# STB_UID.net
KiCad netlist of a schematic drawn in Altium Designer
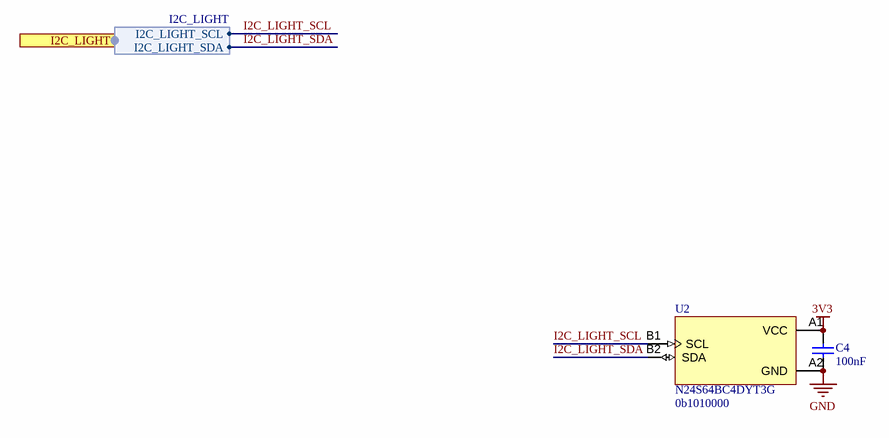
[diagram p0: STB_UID.SchDoc]

(export (version "E")
  (design (tool "Eeschema 10.0.6"))
  (components
    (comp (ref "C4")
      (value "100nF")
      (footprint "CAPC1050X55X23LL05T13")
      (description "Chip Capacitor, 100 nF, +/- 10%, 16 V, -55 to 125 degC, 0402 (1005 Metric), RoHS, Tape and Reel")
      (fields
        (field (name "MANUFACTURER") "Samsung Electro-Mechanics")
        (field (name "MANUFACTURER PART NUMBER") "CL05B104KO5NNNC")
      )
      (libsource (lib "Altium Content Vault") (part "CAP-NP-2"))
    )
    (comp (ref "U2")
      (value "N24S64BC4DYT3G")
      (footprint "4-WLCSP (0.77x0.77)")
      (description "Memory IC 64Kb (8K x 8) I²C 1 MHz 400 ns 4-WLCSP (0.77x0.77)")
      (fields (field (name "MFR") "onsemi") (field (name "MANUFACTURER") "ON Semiconductor"))
      (libsource (lib "ETHZ Vault") (part "N24S64BC4DYT3G"))
    )
  )
  (nets
    (net (code "2") (name "/I2C_LIGHT_SCL") (class "Default")
      (node (ref "U2") (pin "B1") (pinfunction "SCL_B1") (pintype "input"))
    )
    (net (code "3") (name "/I2C_LIGHT_SDA") (class "Default")
      (node (ref "U2") (pin "B2") (pinfunction "SDA_B2") (pintype "bidirectional"))
    )
    (net (code "5") (name "3V3") (class "Default")
      (node (ref "C4") (pin "2") (pinfunction "2_2") (pintype "passive"))
      (node (ref "U2") (pin "A1") (pinfunction "VCC_A1") (pintype "power_in"))
    )
    (net (code "6") (name "GND") (class "Default")
      (node (ref "C4") (pin "1") (pinfunction "1_1") (pintype "passive"))
      (node (ref "U2") (pin "A2") (pinfunction "GND_A2") (pintype "power_in"))
    )
  )
)
